# opendtu_V2.net
KiCad netlist of a schematic drawn in EAGLE
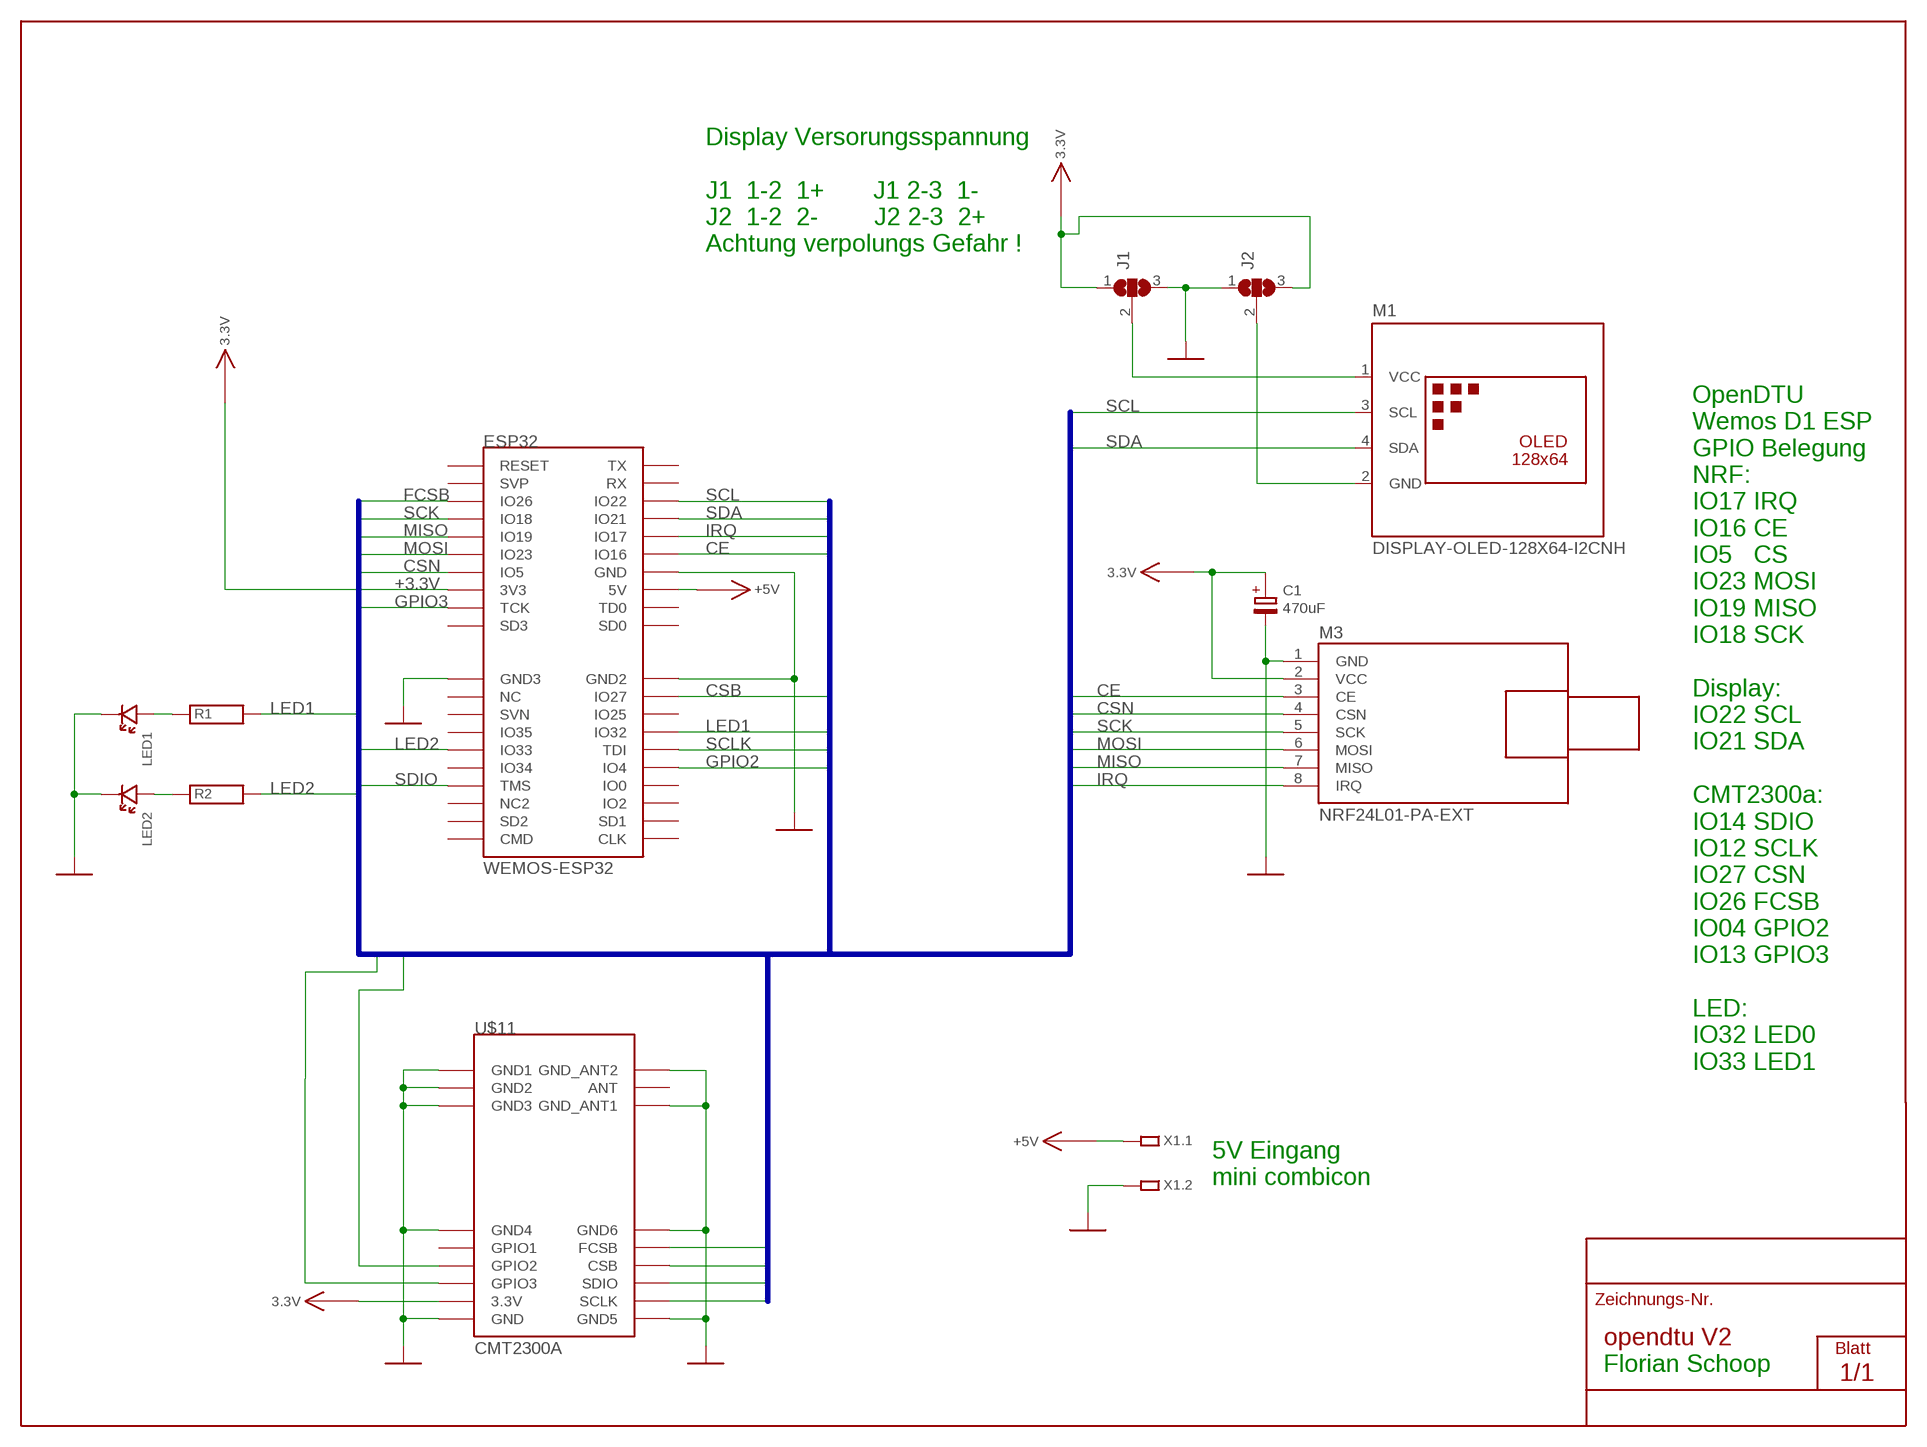
[diagram p0: schematic, sheet 1]

(export (version "E")
  (design (tool "Eeschema 10.0.6"))
  (components
    (comp (ref "C1")
      (value "470uF")
      (footprint "eagle-import:EB10D")
      (libsource (lib "eagle-import") (part "S470µ/16"))
    )
    (comp (ref "ESP32")
      (value "WEMOS-ESP32")
      (footprint "eagle-import:WEMOS-ESP32")
      (libsource (lib "eagle-import") (part "WEMOS-ESP32"))
    )
    (comp (ref "J1")
      (value "SJ2W")
      (footprint "eagle-import:SJ_2")
      (libsource (lib "eagle-import") (part "SJ2W"))
    )
    (comp (ref "J2")
      (value "SJ2W")
      (footprint "eagle-import:SJ_2")
      (libsource (lib "eagle-import") (part "SJ2W"))
    )
    (comp (ref "LED1")
      (value "LED3MM")
      (footprint "eagle-import:LED3MM")
      (libsource (lib "eagle-import") (part "LED3MM"))
    )
    (comp (ref "LED2")
      (value "LED3MM")
      (footprint "eagle-import:LED3MM")
      (libsource (lib "eagle-import") (part "LED3MM"))
    )
    (comp (ref "M1")
      (value "DISPLAY-OLED-128X64-I2CNH")
      (footprint "eagle-import:DISPLAY-OLED-128X64-I2C_NH")
      (libsource (lib "eagle-import") (part "DISPLAY-OLED-128X64-I2CNH"))
    )
    (comp (ref "M3")
      (value "NRF24L01-PA-EXT")
      (footprint "eagle-import:NRF24L01-PA-EXT")
      (libsource (lib "eagle-import") (part "NRF24L01-PA-EXT"))
    )
    (comp (ref "R1")
      (value "WIDERSAND")
      (footprint "eagle-import:1_8W")
      (libsource (lib "eagle-import") (part "WIDERSAND"))
    )
    (comp (ref "R2")
      (value "WIDERSAND")
      (footprint "eagle-import:1_8W")
      (libsource (lib "eagle-import") (part "WIDERSAND"))
    )
    (comp (ref "U$11")
      (value "CMT2300A")
      (footprint "eagle-import:CMT2300A")
      (libsource (lib "eagle-import") (part "CMT2300A"))
    )
    (comp (ref "X1")
      (value "MCV1,5/2G")
      (footprint "eagle-import:MCV1,5_2")
      (libsource (lib "eagle-import") (part "MCV1,5/2G"))
    )
  )
  (nets
    (net (code "1") (name "+5V") (class "Default")
      (node (ref "ESP32") (pin "VCC") (pinfunction "5V_VCC") (pintype "bidirectional"))
      (node (ref "X1") (pin "1") (pinfunction "1_1") (pintype "bidirectional"))
    )
    (net (code "2") (name "/CE") (class "Default")
      (node (ref "ESP32") (pin "IO16") (pinfunction "IO16_IO16") (pintype "bidirectional"))
      (node (ref "M3") (pin "3") (pinfunction "CE_3") (pintype "bidirectional"))
    )
    (net (code "3") (name "/CSB") (class "Default")
      (node (ref "ESP32") (pin "IO27") (pinfunction "IO27_IO27") (pintype "bidirectional"))
      (node (ref "U$11") (pin "CSB") (pinfunction "CSB_CSB") (pintype "bidirectional"))
    )
    (net (code "4") (name "/CSN") (class "Default")
      (node (ref "ESP32") (pin "IO5") (pinfunction "IO5_IO5") (pintype "bidirectional"))
      (node (ref "M3") (pin "4") (pinfunction "CSN_4") (pintype "bidirectional"))
    )
    (net (code "5") (name "/FCSB") (class "Default")
      (node (ref "ESP32") (pin "IO26") (pinfunction "IO26_IO26") (pintype "bidirectional"))
      (node (ref "U$11") (pin "FCSB") (pinfunction "FCSB_FCSB") (pintype "bidirectional"))
    )
    (net (code "6") (name "/GPIO2") (class "Default")
      (node (ref "ESP32") (pin "IO4") (pinfunction "IO4_IO4") (pintype "bidirectional"))
      (node (ref "U$11") (pin "GPIO2") (pinfunction "GPIO2_GPIO2") (pintype "bidirectional"))
    )
    (net (code "7") (name "/GPIO3") (class "Default")
      (node (ref "ESP32") (pin "TCK") (pinfunction "TCK_TCK") (pintype "bidirectional"))
      (node (ref "U$11") (pin "GPIO3") (pinfunction "GPIO3_GPIO3") (pintype "bidirectional"))
    )
    (net (code "8") (name "/IRQ") (class "Default")
      (node (ref "ESP32") (pin "IO17") (pinfunction "IO17_IO17") (pintype "bidirectional"))
      (node (ref "M3") (pin "8") (pinfunction "IRQ_8") (pintype "bidirectional"))
    )
    (net (code "9") (name "/LED1") (class "Default")
      (node (ref "ESP32") (pin "IO32") (pinfunction "IO32_IO32") (pintype "bidirectional"))
      (node (ref "R1") (pin "2") (pinfunction "2_2") (pintype "passive"))
    )
    (net (code "10") (name "/LED2") (class "Default")
      (node (ref "ESP32") (pin "IO33") (pinfunction "IO33_IO33") (pintype "bidirectional"))
      (node (ref "R2") (pin "2") (pinfunction "2_2") (pintype "passive"))
    )
    (net (code "11") (name "/MISO") (class "Default")
      (node (ref "ESP32") (pin "IO19") (pinfunction "IO19_IO19") (pintype "bidirectional"))
      (node (ref "M3") (pin "7") (pinfunction "MISO_7") (pintype "bidirectional"))
    )
    (net (code "12") (name "/MOSI") (class "Default")
      (node (ref "ESP32") (pin "IO23") (pinfunction "IO23_IO23") (pintype "bidirectional"))
      (node (ref "M3") (pin "6") (pinfunction "MOSI_6") (pintype "bidirectional"))
    )
    (net (code "13") (name "/SCK") (class "Default")
      (node (ref "ESP32") (pin "IO18") (pinfunction "IO18_IO18") (pintype "bidirectional"))
      (node (ref "M3") (pin "5") (pinfunction "SCK_5") (pintype "bidirectional"))
    )
    (net (code "14") (name "/SCL") (class "Default")
      (node (ref "ESP32") (pin "IO22") (pinfunction "IO22_IO22") (pintype "bidirectional"))
      (node (ref "M1") (pin "3") (pinfunction "SCL_3") (pintype "bidirectional"))
    )
    (net (code "15") (name "/SCLK") (class "Default")
      (node (ref "ESP32") (pin "TDI") (pinfunction "TDI_TDI") (pintype "bidirectional"))
      (node (ref "U$11") (pin "SCLK") (pinfunction "SCLK_SCLK") (pintype "bidirectional"))
    )
    (net (code "16") (name "/SDA") (class "Default")
      (node (ref "ESP32") (pin "IO21") (pinfunction "IO21_IO21") (pintype "bidirectional"))
      (node (ref "M1") (pin "4") (pinfunction "SDA_4") (pintype "bidirectional"))
    )
    (net (code "17") (name "/SDIO") (class "Default")
      (node (ref "ESP32") (pin "TMS") (pinfunction "TMS_TMS") (pintype "bidirectional"))
      (node (ref "U$11") (pin "SDIO") (pinfunction "SDIO_SDIO") (pintype "bidirectional"))
    )
    (net (code "18") (name "3.3V") (class "Default")
      (node (ref "C1") (pin "+") (pinfunction "+_+") (pintype "passive"))
      (node (ref "ESP32") (pin "3V3") (pinfunction "3V3_3V3") (pintype "bidirectional"))
      (node (ref "J1") (pin "1") (pinfunction "1_1") (pintype "passive"))
      (node (ref "J2") (pin "3") (pinfunction "3_3") (pintype "passive"))
      (node (ref "M3") (pin "2") (pinfunction "VCC_2") (pintype "power_in"))
      (node (ref "U$11") (pin "3.3V") (pinfunction "3.3V_3.3V") (pintype "bidirectional"))
    )
    (net (code "19") (name "GND") (class "Default")
      (node (ref "C1") (pin "-") (pinfunction "-_-") (pintype "passive"))
      (node (ref "ESP32") (pin "GND") (pinfunction "GND_GND") (pintype "bidirectional"))
      (node (ref "ESP32") (pin "GND2") (pinfunction "GND2_GND2") (pintype "bidirectional"))
      (node (ref "ESP32") (pin "GND3") (pinfunction "GND3_GND3") (pintype "bidirectional"))
      (node (ref "J1") (pin "3") (pinfunction "3_3") (pintype "passive"))
      (node (ref "J2") (pin "1") (pinfunction "1_1") (pintype "passive"))
      (node (ref "LED1") (pin "K") (pinfunction "KAT_K") (pintype "passive"))
      (node (ref "LED2") (pin "K") (pinfunction "KAT_K") (pintype "passive"))
      (node (ref "M3") (pin "1") (pinfunction "GND_1") (pintype "power_in"))
      (node (ref "U$11") (pin "GND") (pinfunction "GND_GND") (pintype "bidirectional"))
      (node (ref "U$11") (pin "GND1") (pinfunction "GND1_GND1") (pintype "bidirectional"))
      (node (ref "U$11") (pin "GND2") (pinfunction "GND2_GND2") (pintype "bidirectional"))
      (node (ref "U$11") (pin "GND3") (pinfunction "GND3_GND3") (pintype "bidirectional"))
      (node (ref "U$11") (pin "GND4") (pinfunction "GND4_GND4") (pintype "bidirectional"))
      (node (ref "U$11") (pin "GND5") (pinfunction "GND5_GND5") (pintype "bidirectional"))
      (node (ref "U$11") (pin "GND6") (pinfunction "GND6_GND6") (pintype "bidirectional"))
      (node (ref "U$11") (pin "GND_ANT1") (pinfunction "GND_ANT1_GND_ANT1") (pintype "bidirectional"))
      (node (ref "U$11") (pin "GND_ANT2") (pinfunction "GND_ANT2_GND_ANT2") (pintype "bidirectional"))
      (node (ref "X1") (pin "2") (pinfunction "1_2") (pintype "bidirectional"))
    )
    (net (code "20") (name "Net-(LED1-ANO)") (class "Default")
      (node (ref "LED1") (pin "A") (pinfunction "ANO_A") (pintype "passive"))
      (node (ref "R1") (pin "1") (pinfunction "1_1") (pintype "passive"))
    )
    (net (code "21") (name "Net-(LED2-ANO)") (class "Default")
      (node (ref "LED2") (pin "A") (pinfunction "ANO_A") (pintype "passive"))
      (node (ref "R2") (pin "1") (pinfunction "1_1") (pintype "passive"))
    )
    (net (code "22") (name "Net-(M1-GND)") (class "Default")
      (node (ref "J2") (pin "2") (pinfunction "2_2") (pintype "passive"))
      (node (ref "M1") (pin "2") (pinfunction "GND_2") (pintype "power_in"))
    )
    (net (code "23") (name "Net-(M1-VCC)") (class "Default")
      (node (ref "J1") (pin "2") (pinfunction "2_2") (pintype "passive"))
      (node (ref "M1") (pin "1") (pinfunction "VCC_1") (pintype "power_in"))
    )
    (net (code "24") (name "unconnected-(ESP32-NC2-PadNC1)") (class "Default")
      (node (ref "ESP32") (pin "NC1") (pinfunction "NC2_NC1") (pintype "bidirectional"))
    )
    (net (code "25") (name "unconnected-(ESP32-PadCLK)") (class "Default")
      (node (ref "ESP32") (pin "CLK") (pinfunction "CLK_CLK") (pintype "bidirectional"))
    )
    (net (code "26") (name "unconnected-(ESP32-PadCMD)") (class "Default")
      (node (ref "ESP32") (pin "CMD") (pinfunction "CMD_CMD") (pintype "bidirectional"))
    )
    (net (code "27") (name "unconnected-(ESP32-PadIO0)") (class "Default")
      (node (ref "ESP32") (pin "IO0") (pinfunction "IO0_IO0") (pintype "bidirectional"))
    )
    (net (code "28") (name "unconnected-(ESP32-PadIO2)") (class "Default")
      (node (ref "ESP32") (pin "IO2") (pinfunction "IO2_IO2") (pintype "bidirectional"))
    )
    (net (code "29") (name "unconnected-(ESP32-PadIO25)") (class "Default")
      (node (ref "ESP32") (pin "IO25") (pinfunction "IO25_IO25") (pintype "bidirectional"))
    )
    (net (code "30") (name "unconnected-(ESP32-PadIO34)") (class "Default")
      (node (ref "ESP32") (pin "IO34") (pinfunction "IO34_IO34") (pintype "bidirectional"))
    )
    (net (code "31") (name "unconnected-(ESP32-PadIO35)") (class "Default")
      (node (ref "ESP32") (pin "IO35") (pinfunction "IO35_IO35") (pintype "bidirectional"))
    )
    (net (code "32") (name "unconnected-(ESP32-PadNC)") (class "Default")
      (node (ref "ESP32") (pin "NC") (pinfunction "NC_NC") (pintype "bidirectional"))
    )
    (net (code "33") (name "unconnected-(ESP32-PadSD0)") (class "Default")
      (node (ref "ESP32") (pin "SD0") (pinfunction "SD0_SD0") (pintype "bidirectional"))
    )
    (net (code "34") (name "unconnected-(ESP32-PadSD1)") (class "Default")
      (node (ref "ESP32") (pin "SD1") (pinfunction "SD1_SD1") (pintype "bidirectional"))
    )
    (net (code "35") (name "unconnected-(ESP32-PadSD2)") (class "Default")
      (node (ref "ESP32") (pin "SD2") (pinfunction "SD2_SD2") (pintype "bidirectional"))
    )
    (net (code "36") (name "unconnected-(ESP32-PadSD3)") (class "Default")
      (node (ref "ESP32") (pin "SD3") (pinfunction "SD3_SD3") (pintype "bidirectional"))
    )
    (net (code "37") (name "unconnected-(ESP32-PadSVN)") (class "Default")
      (node (ref "ESP32") (pin "SVN") (pinfunction "SVN_SVN") (pintype "bidirectional"))
    )
    (net (code "38") (name "unconnected-(ESP32-PadSVP)") (class "Default")
      (node (ref "ESP32") (pin "SVP") (pinfunction "SVP_SVP") (pintype "bidirectional"))
    )
    (net (code "39") (name "unconnected-(ESP32-PadTD0)") (class "Default")
      (node (ref "ESP32") (pin "TD0") (pinfunction "TD0_TD0") (pintype "bidirectional"))
    )
    (net (code "40") (name "unconnected-(ESP32-RESET-PadRST)") (class "Default")
      (node (ref "ESP32") (pin "RST") (pinfunction "RESET_RST") (pintype "bidirectional"))
    )
    (net (code "41") (name "unconnected-(ESP32-RX-PadRXD)") (class "Default")
      (node (ref "ESP32") (pin "RXD") (pinfunction "RX_RXD") (pintype "bidirectional"))
    )
    (net (code "42") (name "unconnected-(ESP32-TX-PadTXD)") (class "Default")
      (node (ref "ESP32") (pin "TXD") (pinfunction "TX_TXD") (pintype "bidirectional"))
    )
    (net (code "43") (name "unconnected-(U$11-PadANT)") (class "Default")
      (node (ref "U$11") (pin "ANT") (pinfunction "ANT_ANT") (pintype "bidirectional"))
    )
    (net (code "44") (name "unconnected-(U$11-PadGPIO1)") (class "Default")
      (node (ref "U$11") (pin "GPIO1") (pinfunction "GPIO1_GPIO1") (pintype "bidirectional"))
    )
  )
)
